# facetHound_inputs_chassis_v12.net
KiCad netlist of a schematic drawn in EAGLE
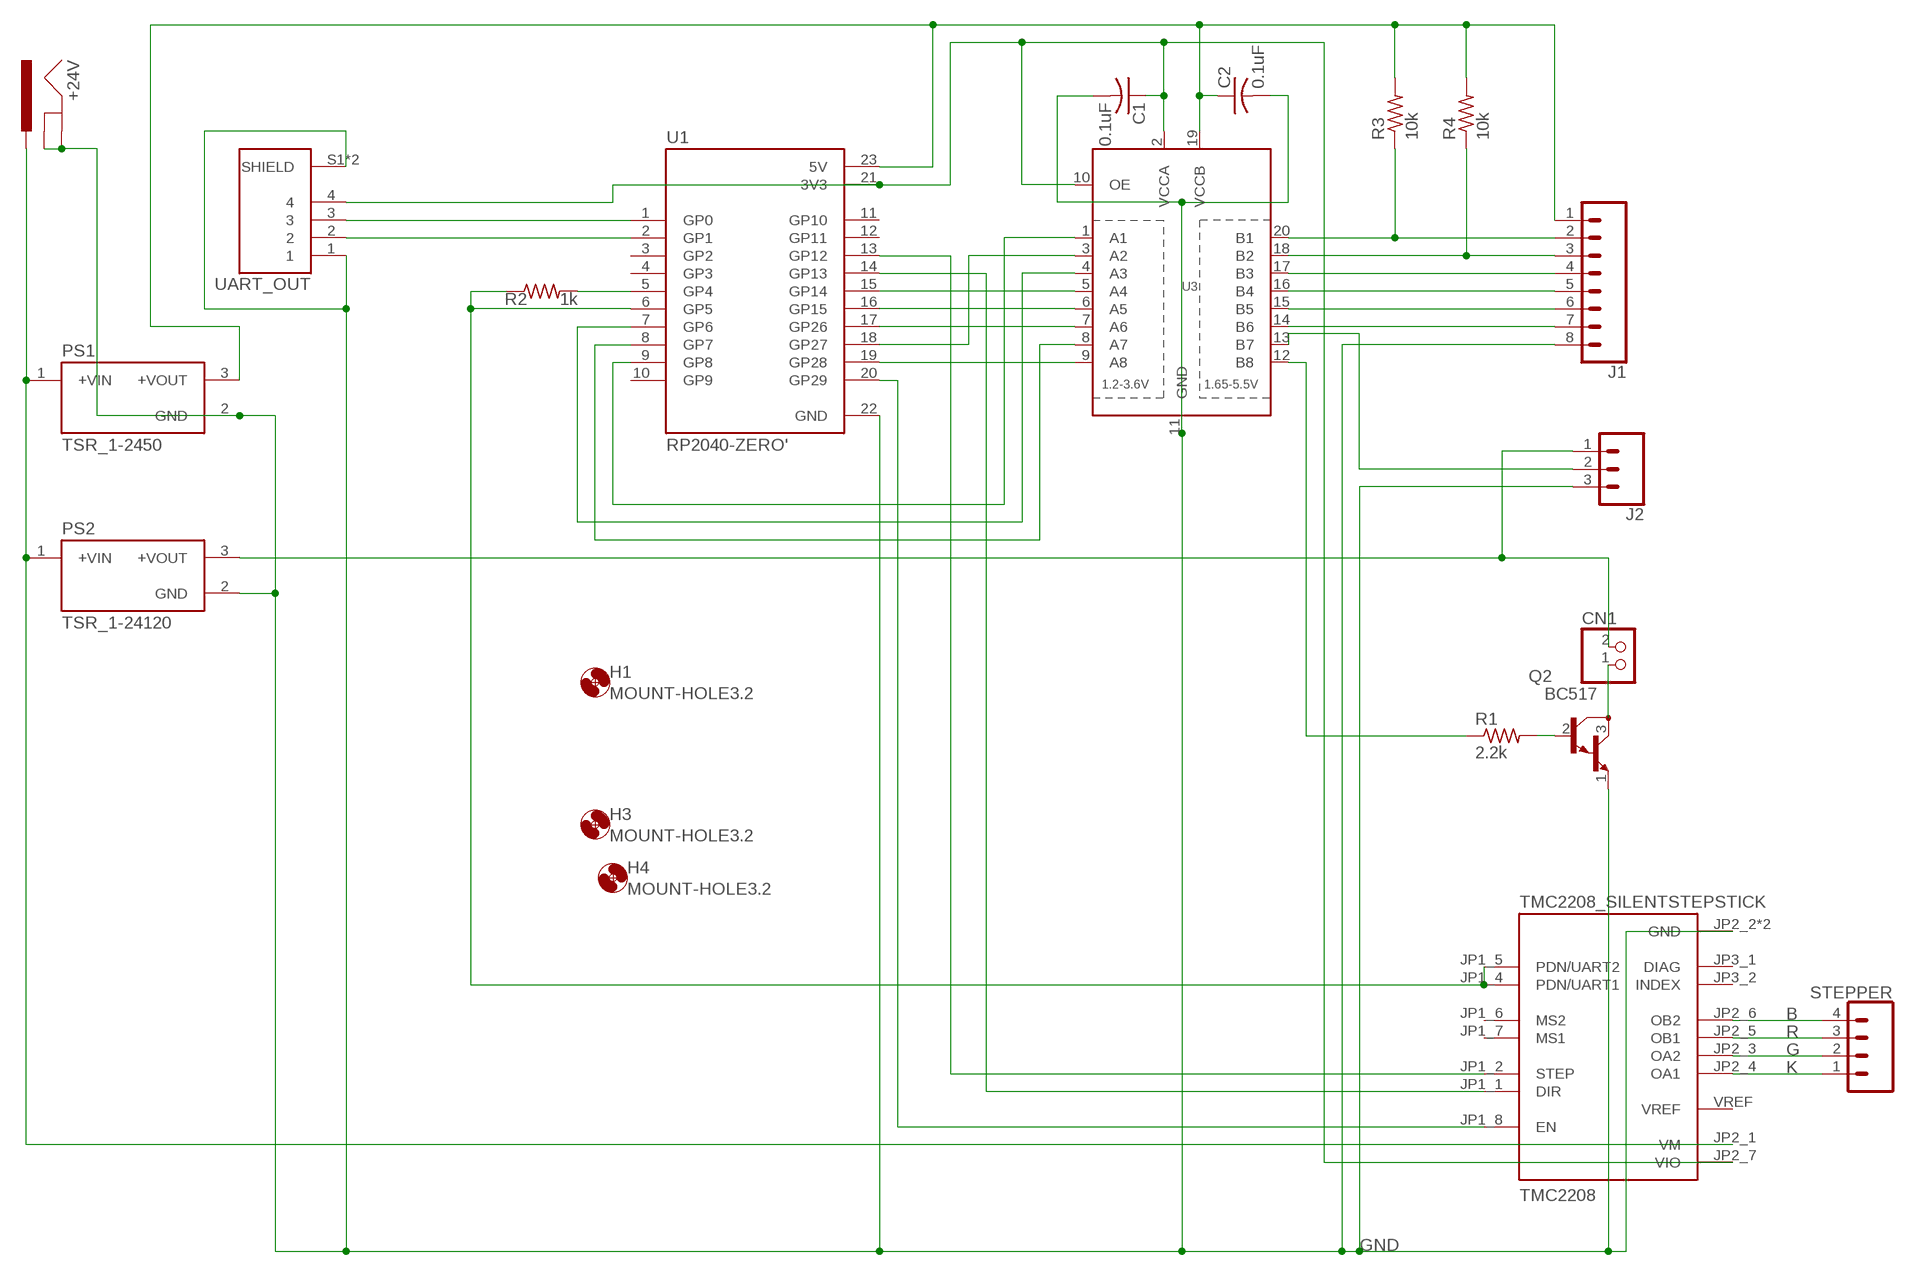
[diagram p0: schematic, sheet 1]

(export (version "E")
  (design (tool "Eeschema 10.0.6"))
  (components
    (comp (ref "+24V")
      (value "POWER_JACKPOWER_JACK_SLOT")
      (footprint "eagle-import:POWER_JACK_PTH_SLOT")
      (libsource (lib "eagle-import") (part "POWER_JACKPOWER_JACK_SLOT"))
    )
    (comp (ref "C1")
      (value "0.1uF")
      (footprint "eagle-import:C1206")
      (libsource (lib "eagle-import") (part "C-USC1206"))
    )
    (comp (ref "C2")
      (value "0.1uF")
      (footprint "eagle-import:C1206")
      (libsource (lib "eagle-import") (part "C-USC1206"))
    )
    (comp (ref "CN1")
      (value "JST_2PIN-THM-RA")
      (footprint "eagle-import:JST-PH-2-THM-RA")
      (libsource (lib "eagle-import") (part "JST_2PIN-THM-RA"))
    )
    (comp (ref "H1")
      (value "MOUNT-HOLE3.2")
      (footprint "eagle-import:3,2")
      (libsource (lib "eagle-import") (part "MOUNT-HOLE3.2"))
    )
    (comp (ref "H3")
      (value "MOUNT-HOLE3.2")
      (footprint "eagle-import:3,2")
      (libsource (lib "eagle-import") (part "MOUNT-HOLE3.2"))
    )
    (comp (ref "H4")
      (value "MOUNT-HOLE3.2")
      (footprint "eagle-import:3,2")
      (libsource (lib "eagle-import") (part "MOUNT-HOLE3.2"))
    )
    (comp (ref "J1")
      (value "CONN_08LONGPADS")
      (footprint "eagle-import:1X08_LONGPADS")
      (libsource (lib "eagle-import") (part "CONN_08LONGPADS"))
    )
    (comp (ref "J2")
      (value "CONN_03SCREW")
      (footprint "eagle-import:SCREWTERMINAL-3.5MM-3")
      (libsource (lib "eagle-import") (part "CONN_03SCREW"))
    )
    (comp (ref "PS1")
      (value "TSR_1-2450")
      (footprint "eagle-import:CONV_TSR_1-2450")
      (fields (field (name "MANUFACTURER") "Traco Power"))
      (libsource (lib "eagle-import") (part "TSR_1-2450"))
    )
    (comp (ref "PS2")
      (value "TSR_1-24120")
      (footprint "eagle-import:CONV_TSR_1-2450")
      (fields (field (name "MANUFACTURER") "Traco Power"))
      (libsource (lib "eagle-import") (part "TSR_1-2450"))
    )
    (comp (ref "Q2")
      (value "BC517")
      (footprint "eagle-import:TO92")
      (libsource (lib "eagle-import") (part "BC517"))
    )
    (comp (ref "R1")
      (value "2.2k")
      (footprint "eagle-import:M1206")
      (libsource (lib "eagle-import") (part "R-US_M1206"))
    )
    (comp (ref "R2")
      (value "1k")
      (footprint "eagle-import:R1206")
      (libsource (lib "eagle-import") (part "R-US_R1206"))
    )
    (comp (ref "R3")
      (value "10k")
      (footprint "eagle-import:M1206")
      (libsource (lib "eagle-import") (part "R-US_M1206"))
    )
    (comp (ref "R4")
      (value "10k")
      (footprint "eagle-import:M1206")
      (libsource (lib "eagle-import") (part "R-US_M1206"))
    )
    (comp (ref "STEPPER")
      (value "CONN_04JST-PTH")
      (footprint "eagle-import:JST-4-PTH")
      (libsource (lib "eagle-import") (part "CONN_04JST-PTH"))
    )
    (comp (ref "TMC2208")
      (value "TMC2208_SILENTSTEPSTICK")
      (footprint "eagle-import:MODULE_TMC2208_SILENTSTEPSTICK")
      (fields (field (name "MF") "Trinamic Motion") (field (name "MP") "TMC2208 SILENTSTEPSTICK"))
      (libsource (lib "eagle-import") (part "TMC2208_SILENTSTEPSTICK"))
    )
    (comp (ref "U1")
      (value "RP2040-ZERO'")
      (footprint "eagle-import:MODULE_RP2040-ZERO")
      (fields (field (name "MF") "Waveshare Electronics") (field (name "MP") "RP2040-ZERO"))
      (libsource (lib "eagle-import") (part "RP2040-ZERO'"))
    )
    (comp (ref "U3")
      (value "TXB0108PWR")
      (footprint "eagle-import:TSSOP20")
      (libsource (lib "eagle-import") (part "TXB0108PWR"))
    )
    (comp (ref "UART_OUT")
      (value "S4B-ZR-SM4A-TF(LF)(SN)")
      (footprint "eagle-import:JST_S4B-ZR-SM4A-TF(LF)(SN)")
      (fields (field (name "MF") "JST Sales"))
      (libsource (lib "eagle-import") (part "S4B-ZR-SM4A-TF(LF)(SN)"))
    )
  )
  (nets
    (net (code "1") (name "B") (class "Default")
      (node (ref "STEPPER") (pin "4") (pinfunction "4_4") (pintype "passive"))
      (node (ref "TMC2208") (pin "JP2_6") (pinfunction "OB2_JP2_6") (pintype "passive"))
    )
    (net (code "2") (name "G") (class "Default")
      (node (ref "STEPPER") (pin "2") (pinfunction "2_2") (pintype "passive"))
      (node (ref "TMC2208") (pin "JP2_3") (pinfunction "OA2_JP2_3") (pintype "passive"))
    )
    (net (code "3") (name "GND") (class "Default")
      (node (ref "+24V") (pin "GND") (pinfunction "GND_GND") (pintype "bidirectional"))
      (node (ref "+24V") (pin "GNDBREAK") (pinfunction "GNDBREAK_GNDBREAK") (pintype "bidirectional"))
      (node (ref "C1") (pin "2") (pinfunction "2_2") (pintype "passive"))
      (node (ref "C2") (pin "2") (pinfunction "2_2") (pintype "passive"))
      (node (ref "J1") (pin "8") (pinfunction "8_8") (pintype "passive"))
      (node (ref "J2") (pin "3") (pinfunction "3_3") (pintype "passive"))
      (node (ref "PS1") (pin "2") (pinfunction "GND_2") (pintype "power_in"))
      (node (ref "PS2") (pin "2") (pinfunction "GND_2") (pintype "power_in"))
      (node (ref "Q2") (pin "1") (pinfunction "E_1") (pintype "passive"))
      (node (ref "TMC2208") (pin "JP2_2") (pinfunction "GND_JP2_2") (pintype "power_in"))
      (node (ref "TMC2208") (pin "JP2_8") (pinfunction "GND_JP2_8") (pintype "power_in"))
      (node (ref "U1") (pin "22") (pinfunction "GND_22") (pintype "power_in"))
      (node (ref "U3") (pin "11") (pinfunction "GND_11") (pintype "bidirectional"))
      (node (ref "UART_OUT") (pin "1") (pinfunction "1_1") (pintype "passive"))
      (node (ref "UART_OUT") (pin "S1") (pinfunction "SHIELD_S1") (pintype "passive"))
      (node (ref "UART_OUT") (pin "S2") (pinfunction "SHIELD_S2") (pintype "passive"))
    )
    (net (code "4") (name "K") (class "Default")
      (node (ref "STEPPER") (pin "1") (pinfunction "1_1") (pintype "passive"))
      (node (ref "TMC2208") (pin "JP2_4") (pinfunction "OA1_JP2_4") (pintype "passive"))
    )
    (net (code "5") (name "Net-(CN1-1)") (class "Default")
      (node (ref "CN1") (pin "2") (pinfunction "1_2") (pintype "passive"))
      (node (ref "J2") (pin "1") (pinfunction "1_1") (pintype "passive"))
      (node (ref "PS2") (pin "3") (pinfunction "+VOUT_3") (pintype "output"))
    )
    (net (code "6") (name "Net-(CN1-2)") (class "Default")
      (node (ref "CN1") (pin "1") (pinfunction "2_1") (pintype "passive"))
      (node (ref "Q2") (pin "3") (pinfunction "C_3") (pintype "passive"))
    )
    (net (code "7") (name "Net-(PS1-+VIN)") (class "Default")
      (node (ref "+24V") (pin "PWR") (pinfunction "PWR_PWR") (pintype "bidirectional"))
      (node (ref "PS1") (pin "1") (pinfunction "+VIN_1") (pintype "input"))
      (node (ref "PS2") (pin "1") (pinfunction "+VIN_1") (pintype "input"))
      (node (ref "TMC2208") (pin "JP2_1") (pinfunction "VM_JP2_1") (pintype "power_in"))
    )
    (net (code "8") (name "Net-(PS1-+VOUT)") (class "Default")
      (node (ref "C2") (pin "1") (pinfunction "1_1") (pintype "passive"))
      (node (ref "J1") (pin "1") (pinfunction "1_1") (pintype "passive"))
      (node (ref "PS1") (pin "3") (pinfunction "+VOUT_3") (pintype "output"))
      (node (ref "R3") (pin "2") (pinfunction "2_2") (pintype "passive"))
      (node (ref "R4") (pin "2") (pinfunction "2_2") (pintype "passive"))
      (node (ref "U1") (pin "23") (pinfunction "5V_23") (pintype "power_in"))
      (node (ref "U3") (pin "19") (pinfunction "VCCB_19") (pintype "bidirectional"))
    )
    (net (code "9") (name "Net-(Q2-B)") (class "Default")
      (node (ref "Q2") (pin "2") (pinfunction "B_2") (pintype "passive"))
      (node (ref "R1") (pin "2") (pinfunction "2_2") (pintype "passive"))
    )
    (net (code "10") (name "Net-(TMC2208-DIR)") (class "Default")
      (node (ref "TMC2208") (pin "JP1_1") (pinfunction "DIR_JP1_1") (pintype "input"))
      (node (ref "U1") (pin "14") (pinfunction "GP13_14") (pintype "bidirectional"))
    )
    (net (code "11") (name "Net-(TMC2208-EN)") (class "Default")
      (node (ref "TMC2208") (pin "JP1_8") (pinfunction "EN_JP1_8") (pintype "input"))
      (node (ref "U1") (pin "20") (pinfunction "GP29_20") (pintype "bidirectional"))
    )
    (net (code "12") (name "Net-(TMC2208-PDN{slash}UART1)") (class "Default")
      (node (ref "R2") (pin "1") (pinfunction "1_1") (pintype "passive"))
      (node (ref "TMC2208") (pin "JP1_4") (pinfunction "PDN/UART1_JP1_4") (pintype "bidirectional"))
      (node (ref "TMC2208") (pin "JP1_5") (pinfunction "PDN/UART2_JP1_5") (pintype "bidirectional"))
      (node (ref "U1") (pin "6") (pinfunction "GP5_6") (pintype "bidirectional"))
    )
    (net (code "13") (name "Net-(TMC2208-STEP)") (class "Default")
      (node (ref "TMC2208") (pin "JP1_2") (pinfunction "STEP_JP1_2") (pintype "input"))
      (node (ref "U1") (pin "13") (pinfunction "GP12_13") (pintype "bidirectional"))
    )
    (net (code "14") (name "Net-(TMC2208-VIO)") (class "Default")
      (node (ref "C1") (pin "1") (pinfunction "1_1") (pintype "passive"))
      (node (ref "TMC2208") (pin "JP2_7") (pinfunction "VIO_JP2_7") (pintype "power_in"))
      (node (ref "U1") (pin "21") (pinfunction "3V3_21") (pintype "power_in"))
      (node (ref "U3") (pin "10") (pinfunction "OE_10") (pintype "bidirectional"))
      (node (ref "U3") (pin "2") (pinfunction "VCCA_2") (pintype "bidirectional"))
      (node (ref "UART_OUT") (pin "4") (pinfunction "4_4") (pintype "passive"))
    )
    (net (code "15") (name "Net-(U1-GP0)") (class "Default")
      (node (ref "U1") (pin "1") (pinfunction "GP0_1") (pintype "bidirectional"))
      (node (ref "UART_OUT") (pin "3") (pinfunction "3_3") (pintype "passive"))
    )
    (net (code "16") (name "Net-(U1-GP1)") (class "Default")
      (node (ref "U1") (pin "2") (pinfunction "GP1_2") (pintype "bidirectional"))
      (node (ref "UART_OUT") (pin "2") (pinfunction "2_2") (pintype "passive"))
    )
    (net (code "17") (name "Net-(U1-GP4)") (class "Default")
      (node (ref "R2") (pin "2") (pinfunction "2_2") (pintype "passive"))
      (node (ref "U1") (pin "5") (pinfunction "GP4_5") (pintype "bidirectional"))
    )
    (net (code "18") (name "Net-(U1-GP6)") (class "Default")
      (node (ref "U1") (pin "7") (pinfunction "GP6_7") (pintype "bidirectional"))
      (node (ref "U3") (pin "4") (pinfunction "A3_4") (pintype "bidirectional"))
    )
    (net (code "19") (name "Net-(U1-GP7)") (class "Default")
      (node (ref "U1") (pin "8") (pinfunction "GP7_8") (pintype "bidirectional"))
      (node (ref "U3") (pin "8") (pinfunction "A7_8") (pintype "bidirectional"))
    )
    (net (code "20") (name "Net-(U1-GP8)") (class "Default")
      (node (ref "U1") (pin "9") (pinfunction "GP8_9") (pintype "bidirectional"))
      (node (ref "U3") (pin "1") (pinfunction "A1_1") (pintype "bidirectional"))
    )
    (net (code "21") (name "Net-(U1-GP14)") (class "Default")
      (node (ref "U1") (pin "15") (pinfunction "GP14_15") (pintype "bidirectional"))
      (node (ref "U3") (pin "5") (pinfunction "A4_5") (pintype "bidirectional"))
    )
    (net (code "22") (name "Net-(U1-GP15)") (class "Default")
      (node (ref "U1") (pin "16") (pinfunction "GP15_16") (pintype "bidirectional"))
      (node (ref "U3") (pin "6") (pinfunction "A5_6") (pintype "bidirectional"))
    )
    (net (code "23") (name "Net-(U1-GP26)") (class "Default")
      (node (ref "U1") (pin "17") (pinfunction "GP26_17") (pintype "bidirectional"))
      (node (ref "U3") (pin "7") (pinfunction "A6_7") (pintype "bidirectional"))
    )
    (net (code "24") (name "Net-(U1-GP27)") (class "Default")
      (node (ref "U1") (pin "18") (pinfunction "GP27_18") (pintype "bidirectional"))
      (node (ref "U3") (pin "3") (pinfunction "A2_3") (pintype "bidirectional"))
    )
    (net (code "25") (name "Net-(U1-GP28)") (class "Default")
      (node (ref "U1") (pin "19") (pinfunction "GP28_19") (pintype "bidirectional"))
      (node (ref "U3") (pin "9") (pinfunction "A8_9") (pintype "bidirectional"))
    )
    (net (code "26") (name "Net-(U3-B1)") (class "Default")
      (node (ref "J1") (pin "2") (pinfunction "2_2") (pintype "passive"))
      (node (ref "R3") (pin "1") (pinfunction "1_1") (pintype "passive"))
      (node (ref "U3") (pin "20") (pinfunction "B1_20") (pintype "bidirectional"))
    )
    (net (code "27") (name "Net-(U3-B2)") (class "Default")
      (node (ref "J1") (pin "3") (pinfunction "3_3") (pintype "passive"))
      (node (ref "R4") (pin "1") (pinfunction "1_1") (pintype "passive"))
      (node (ref "U3") (pin "18") (pinfunction "B2_18") (pintype "bidirectional"))
    )
    (net (code "28") (name "Net-(U3-B3)") (class "Default")
      (node (ref "J1") (pin "4") (pinfunction "4_4") (pintype "passive"))
      (node (ref "U3") (pin "17") (pinfunction "B3_17") (pintype "bidirectional"))
    )
    (net (code "29") (name "Net-(U3-B4)") (class "Default")
      (node (ref "J1") (pin "5") (pinfunction "5_5") (pintype "passive"))
      (node (ref "U3") (pin "16") (pinfunction "B4_16") (pintype "bidirectional"))
    )
    (net (code "30") (name "Net-(U3-B5)") (class "Default")
      (node (ref "J1") (pin "6") (pinfunction "6_6") (pintype "passive"))
      (node (ref "U3") (pin "15") (pinfunction "B5_15") (pintype "bidirectional"))
    )
    (net (code "31") (name "Net-(U3-B6)") (class "Default")
      (node (ref "J1") (pin "7") (pinfunction "7_7") (pintype "passive"))
      (node (ref "U3") (pin "14") (pinfunction "B6_14") (pintype "bidirectional"))
    )
    (net (code "32") (name "Net-(U3-B7)") (class "Default")
      (node (ref "J2") (pin "2") (pinfunction "2_2") (pintype "passive"))
      (node (ref "U3") (pin "13") (pinfunction "B7_13") (pintype "bidirectional"))
    )
    (net (code "33") (name "Net-(U3-B8)") (class "Default")
      (node (ref "R1") (pin "1") (pinfunction "1_1") (pintype "passive"))
      (node (ref "U3") (pin "12") (pinfunction "B8_12") (pintype "bidirectional"))
    )
    (net (code "34") (name "R") (class "Default")
      (node (ref "STEPPER") (pin "3") (pinfunction "3_3") (pintype "passive"))
      (node (ref "TMC2208") (pin "JP2_5") (pinfunction "OB1_JP2_5") (pintype "passive"))
    )
    (net (code "35") (name "unconnected-(TMC2208-DIAG-PadJP3_1)") (class "Default")
      (node (ref "TMC2208") (pin "JP3_1") (pinfunction "DIAG_JP3_1") (pintype "output"))
    )
    (net (code "36") (name "unconnected-(TMC2208-INDEX-PadJP3_2)") (class "Default")
      (node (ref "TMC2208") (pin "JP3_2") (pinfunction "INDEX_JP3_2") (pintype "output"))
    )
    (net (code "37") (name "unconnected-(TMC2208-MS1-PadJP1_7)") (class "Default")
      (node (ref "TMC2208") (pin "JP1_7") (pinfunction "MS1_JP1_7") (pintype "input"))
    )
    (net (code "38") (name "unconnected-(TMC2208-MS2-PadJP1_6)") (class "Default")
      (node (ref "TMC2208") (pin "JP1_6") (pinfunction "MS2_JP1_6") (pintype "input"))
    )
    (net (code "39") (name "unconnected-(TMC2208-PadVREF)") (class "Default")
      (node (ref "TMC2208") (pin "VREF") (pinfunction "VREF_VREF") (pintype "passive"))
    )
    (net (code "40") (name "unconnected-(U1-GP2-Pad3)") (class "Default")
      (node (ref "U1") (pin "3") (pinfunction "GP2_3") (pintype "bidirectional"))
    )
    (net (code "41") (name "unconnected-(U1-GP3-Pad4)") (class "Default")
      (node (ref "U1") (pin "4") (pinfunction "GP3_4") (pintype "bidirectional"))
    )
    (net (code "42") (name "unconnected-(U1-GP9-Pad10)") (class "Default")
      (node (ref "U1") (pin "10") (pinfunction "GP9_10") (pintype "bidirectional"))
    )
    (net (code "43") (name "unconnected-(U1-GP10-Pad11)") (class "Default")
      (node (ref "U1") (pin "11") (pinfunction "GP10_11") (pintype "bidirectional"))
    )
    (net (code "44") (name "unconnected-(U1-GP11-Pad12)") (class "Default")
      (node (ref "U1") (pin "12") (pinfunction "GP11_12") (pintype "bidirectional"))
    )
  )
)
